# Schematic_v26.net
KiCad netlist of a schematic drawn in EAGLE
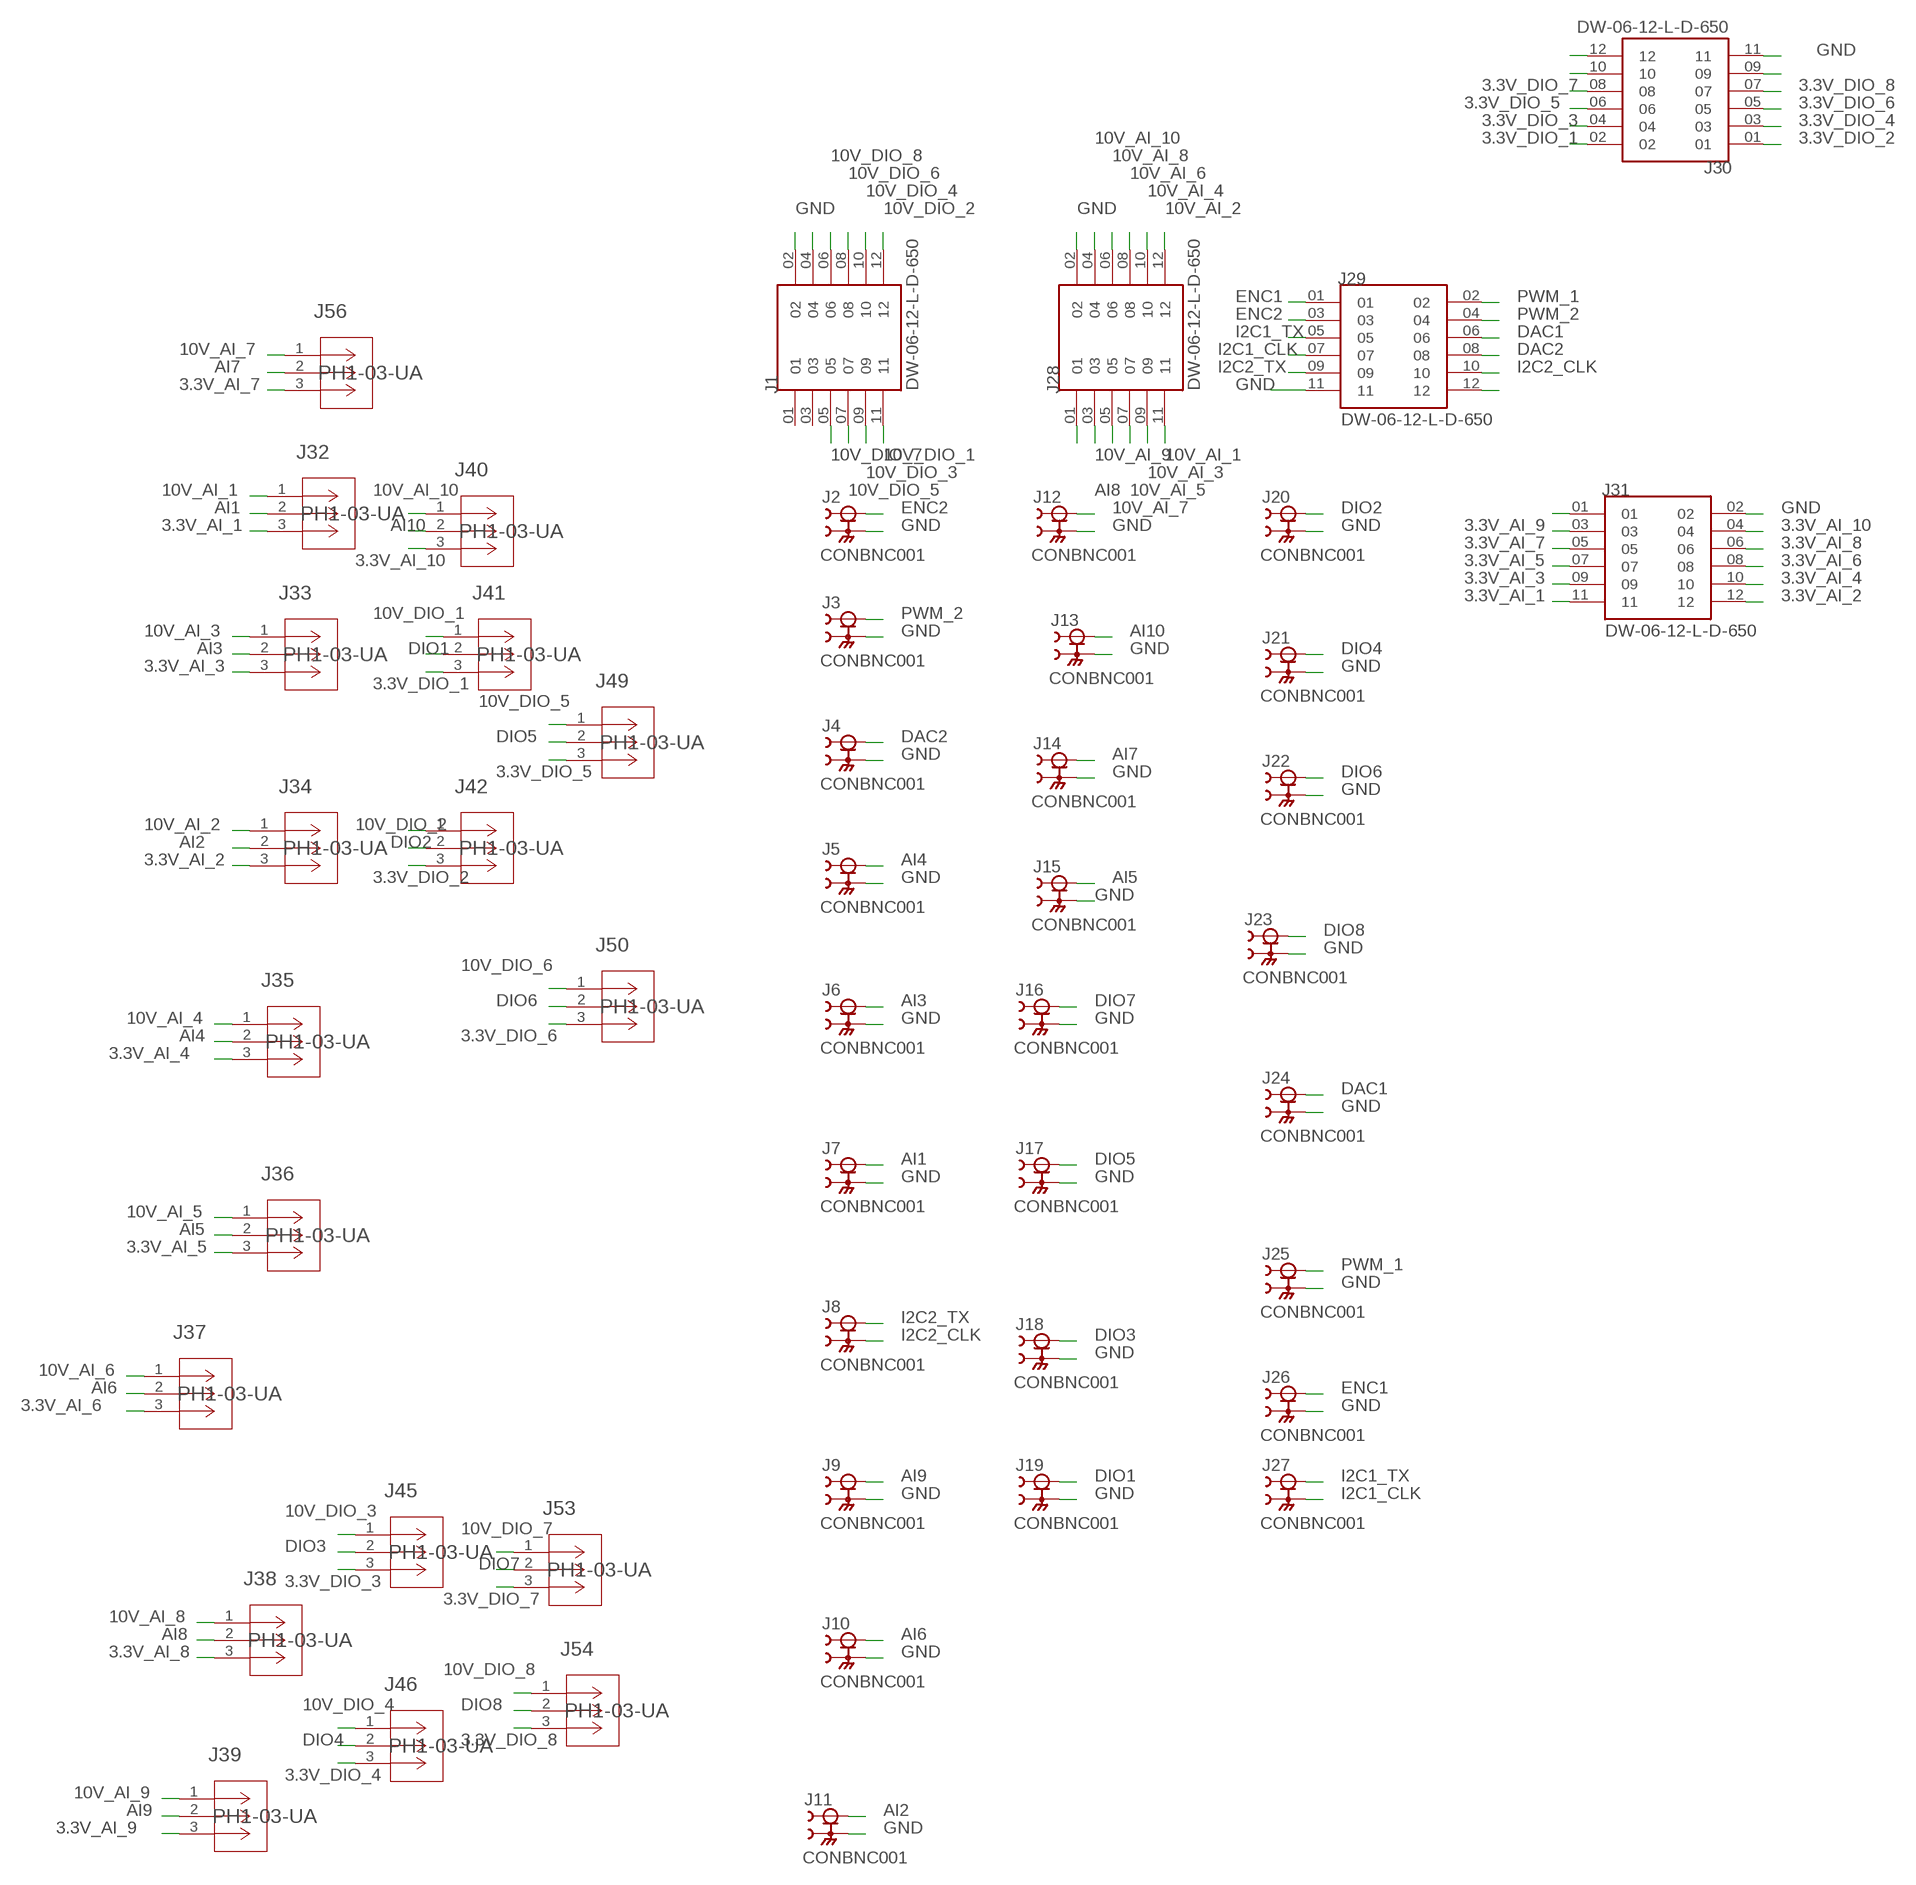
[diagram p0: schematic, sheet 1]

(export (version "E")
  (design (tool "Eeschema 10.0.6"))
  (components
    (comp (ref "J1")
      (value "DW-06-12-L-D-650")
      (footprint "eagle-import:SAMTEC_DW-06-12-L-D-650")
      (fields (field (name "MANUFACTURER") "Samtec"))
      (libsource (lib "eagle-import") (part "DW-06-12-L-D-650"))
    )
    (comp (ref "J2")
      (value "CONBNC001")
      (footprint "eagle-import:LINX_CONBNC001")
      (fields (field (name "MF") "Linx Technologies Inc."))
      (libsource (lib "eagle-import") (part "CONBNC001"))
    )
    (comp (ref "J3")
      (value "CONBNC001")
      (footprint "eagle-import:LINX_CONBNC001")
      (fields (field (name "MF") "Linx Technologies Inc."))
      (libsource (lib "eagle-import") (part "CONBNC001"))
    )
    (comp (ref "J4")
      (value "CONBNC001")
      (footprint "eagle-import:LINX_CONBNC001")
      (fields (field (name "MF") "Linx Technologies Inc."))
      (libsource (lib "eagle-import") (part "CONBNC001"))
    )
    (comp (ref "J5")
      (value "CONBNC001")
      (footprint "eagle-import:LINX_CONBNC001")
      (fields (field (name "MF") "Linx Technologies Inc."))
      (libsource (lib "eagle-import") (part "CONBNC001"))
    )
    (comp (ref "J6")
      (value "CONBNC001")
      (footprint "eagle-import:LINX_CONBNC001")
      (fields (field (name "MF") "Linx Technologies Inc."))
      (libsource (lib "eagle-import") (part "CONBNC001"))
    )
    (comp (ref "J7")
      (value "CONBNC001")
      (footprint "eagle-import:LINX_CONBNC001")
      (fields (field (name "MF") "Linx Technologies Inc."))
      (libsource (lib "eagle-import") (part "CONBNC001"))
    )
    (comp (ref "J8")
      (value "CONBNC001")
      (footprint "eagle-import:LINX_CONBNC001")
      (fields (field (name "MF") "Linx Technologies Inc."))
      (libsource (lib "eagle-import") (part "CONBNC001"))
    )
    (comp (ref "J9")
      (value "CONBNC001")
      (footprint "eagle-import:LINX_CONBNC001")
      (fields (field (name "MF") "Linx Technologies Inc."))
      (libsource (lib "eagle-import") (part "CONBNC001"))
    )
    (comp (ref "J10")
      (value "CONBNC001")
      (footprint "eagle-import:LINX_CONBNC001")
      (fields (field (name "MF") "Linx Technologies Inc."))
      (libsource (lib "eagle-import") (part "CONBNC001"))
    )
    (comp (ref "J11")
      (value "CONBNC001")
      (footprint "eagle-import:LINX_CONBNC001")
      (fields (field (name "MF") "Linx Technologies Inc."))
      (libsource (lib "eagle-import") (part "CONBNC001"))
    )
    (comp (ref "J12")
      (value "CONBNC001")
      (footprint "eagle-import:LINX_CONBNC001")
      (fields (field (name "MF") "Linx Technologies Inc."))
      (libsource (lib "eagle-import") (part "CONBNC001"))
    )
    (comp (ref "J13")
      (value "CONBNC001")
      (footprint "eagle-import:LINX_CONBNC001")
      (fields (field (name "MF") "Linx Technologies Inc."))
      (libsource (lib "eagle-import") (part "CONBNC001"))
    )
    (comp (ref "J14")
      (value "CONBNC001")
      (footprint "eagle-import:LINX_CONBNC001")
      (fields (field (name "MF") "Linx Technologies Inc."))
      (libsource (lib "eagle-import") (part "CONBNC001"))
    )
    (comp (ref "J15")
      (value "CONBNC001")
      (footprint "eagle-import:LINX_CONBNC001")
      (fields (field (name "MF") "Linx Technologies Inc."))
      (libsource (lib "eagle-import") (part "CONBNC001"))
    )
    (comp (ref "J16")
      (value "CONBNC001")
      (footprint "eagle-import:LINX_CONBNC001")
      (fields (field (name "MF") "Linx Technologies Inc."))
      (libsource (lib "eagle-import") (part "CONBNC001"))
    )
    (comp (ref "J17")
      (value "CONBNC001")
      (footprint "eagle-import:LINX_CONBNC001")
      (fields (field (name "MF") "Linx Technologies Inc."))
      (libsource (lib "eagle-import") (part "CONBNC001"))
    )
    (comp (ref "J18")
      (value "CONBNC001")
      (footprint "eagle-import:LINX_CONBNC001")
      (fields (field (name "MF") "Linx Technologies Inc."))
      (libsource (lib "eagle-import") (part "CONBNC001"))
    )
    (comp (ref "J19")
      (value "CONBNC001")
      (footprint "eagle-import:LINX_CONBNC001")
      (fields (field (name "MF") "Linx Technologies Inc."))
      (libsource (lib "eagle-import") (part "CONBNC001"))
    )
    (comp (ref "J20")
      (value "CONBNC001")
      (footprint "eagle-import:LINX_CONBNC001")
      (fields (field (name "MF") "Linx Technologies Inc."))
      (libsource (lib "eagle-import") (part "CONBNC001"))
    )
    (comp (ref "J21")
      (value "CONBNC001")
      (footprint "eagle-import:LINX_CONBNC001")
      (fields (field (name "MF") "Linx Technologies Inc."))
      (libsource (lib "eagle-import") (part "CONBNC001"))
    )
    (comp (ref "J22")
      (value "CONBNC001")
      (footprint "eagle-import:LINX_CONBNC001")
      (fields (field (name "MF") "Linx Technologies Inc."))
      (libsource (lib "eagle-import") (part "CONBNC001"))
    )
    (comp (ref "J23")
      (value "CONBNC001")
      (footprint "eagle-import:LINX_CONBNC001")
      (fields (field (name "MF") "Linx Technologies Inc."))
      (libsource (lib "eagle-import") (part "CONBNC001"))
    )
    (comp (ref "J24")
      (value "CONBNC001")
      (footprint "eagle-import:LINX_CONBNC001")
      (fields (field (name "MF") "Linx Technologies Inc."))
      (libsource (lib "eagle-import") (part "CONBNC001"))
    )
    (comp (ref "J25")
      (value "CONBNC001")
      (footprint "eagle-import:LINX_CONBNC001")
      (fields (field (name "MF") "Linx Technologies Inc."))
      (libsource (lib "eagle-import") (part "CONBNC001"))
    )
    (comp (ref "J26")
      (value "CONBNC001")
      (footprint "eagle-import:LINX_CONBNC001")
      (fields (field (name "MF") "Linx Technologies Inc."))
      (libsource (lib "eagle-import") (part "CONBNC001"))
    )
    (comp (ref "J27")
      (value "CONBNC001")
      (footprint "eagle-import:LINX_CONBNC001")
      (fields (field (name "MF") "Linx Technologies Inc."))
      (libsource (lib "eagle-import") (part "CONBNC001"))
    )
    (comp (ref "J28")
      (value "DW-06-12-L-D-650")
      (footprint "eagle-import:SAMTEC_DW-06-12-L-D-650")
      (fields (field (name "MANUFACTURER") "Samtec"))
      (libsource (lib "eagle-import") (part "DW-06-12-L-D-650"))
    )
    (comp (ref "J29")
      (value "DW-06-12-L-D-650")
      (footprint "eagle-import:SAMTEC_DW-06-12-L-D-650")
      (fields (field (name "MANUFACTURER") "Samtec"))
      (libsource (lib "eagle-import") (part "DW-06-12-L-D-650"))
    )
    (comp (ref "J30")
      (value "DW-06-12-L-D-650")
      (footprint "eagle-import:SAMTEC_DW-06-12-L-D-650")
      (fields (field (name "MANUFACTURER") "Samtec"))
      (libsource (lib "eagle-import") (part "DW-06-12-L-D-650"))
    )
    (comp (ref "J31")
      (value "DW-06-12-L-D-650")
      (footprint "eagle-import:SAMTEC_DW-06-12-L-D-650")
      (fields (field (name "MANUFACTURER") "Samtec"))
      (libsource (lib "eagle-import") (part "DW-06-12-L-D-650"))
    )
    (comp (ref "J32")
      (value "PH1-03-UA")
      (footprint "eagle-import:CONN_PH1-03-UA_ADM")
      (fields (field (name "COPYRIGHT") "Copyright (C) 2025 Ultra Librarian. All rights reserved."))
      (libsource (lib "eagle-import") (part "PH1-03-UA"))
    )
    (comp (ref "J33")
      (value "PH1-03-UA")
      (footprint "eagle-import:CONN_PH1-03-UA_ADM")
      (fields (field (name "COPYRIGHT") "Copyright (C) 2025 Ultra Librarian. All rights reserved."))
      (libsource (lib "eagle-import") (part "PH1-03-UA"))
    )
    (comp (ref "J34")
      (value "PH1-03-UA")
      (footprint "eagle-import:CONN_PH1-03-UA_ADM")
      (fields (field (name "COPYRIGHT") "Copyright (C) 2025 Ultra Librarian. All rights reserved."))
      (libsource (lib "eagle-import") (part "PH1-03-UA"))
    )
    (comp (ref "J35")
      (value "PH1-03-UA")
      (footprint "eagle-import:CONN_PH1-03-UA_ADM")
      (fields (field (name "COPYRIGHT") "Copyright (C) 2025 Ultra Librarian. All rights reserved."))
      (libsource (lib "eagle-import") (part "PH1-03-UA"))
    )
    (comp (ref "J36")
      (value "PH1-03-UA")
      (footprint "eagle-import:CONN_PH1-03-UA_ADM")
      (fields (field (name "COPYRIGHT") "Copyright (C) 2025 Ultra Librarian. All rights reserved."))
      (libsource (lib "eagle-import") (part "PH1-03-UA"))
    )
    (comp (ref "J37")
      (value "PH1-03-UA")
      (footprint "eagle-import:CONN_PH1-03-UA_ADM")
      (fields (field (name "COPYRIGHT") "Copyright (C) 2025 Ultra Librarian. All rights reserved."))
      (libsource (lib "eagle-import") (part "PH1-03-UA"))
    )
    (comp (ref "J38")
      (value "PH1-03-UA")
      (footprint "eagle-import:CONN_PH1-03-UA_ADM")
      (fields (field (name "COPYRIGHT") "Copyright (C) 2025 Ultra Librarian. All rights reserved."))
      (libsource (lib "eagle-import") (part "PH1-03-UA"))
    )
    (comp (ref "J39")
      (value "PH1-03-UA")
      (footprint "eagle-import:CONN_PH1-03-UA_ADM")
      (fields (field (name "COPYRIGHT") "Copyright (C) 2025 Ultra Librarian. All rights reserved."))
      (libsource (lib "eagle-import") (part "PH1-03-UA"))
    )
    (comp (ref "J40")
      (value "PH1-03-UA")
      (footprint "eagle-import:CONN_PH1-03-UA_ADM")
      (fields (field (name "COPYRIGHT") "Copyright (C) 2025 Ultra Librarian. All rights reserved."))
      (libsource (lib "eagle-import") (part "PH1-03-UA"))
    )
    (comp (ref "J41")
      (value "PH1-03-UA")
      (footprint "eagle-import:CONN_PH1-03-UA_ADM")
      (fields (field (name "COPYRIGHT") "Copyright (C) 2025 Ultra Librarian. All rights reserved."))
      (libsource (lib "eagle-import") (part "PH1-03-UA"))
    )
    (comp (ref "J42")
      (value "PH1-03-UA")
      (footprint "eagle-import:CONN_PH1-03-UA_ADM")
      (fields (field (name "COPYRIGHT") "Copyright (C) 2025 Ultra Librarian. All rights reserved."))
      (libsource (lib "eagle-import") (part "PH1-03-UA"))
    )
    (comp (ref "J45")
      (value "PH1-03-UA")
      (footprint "eagle-import:CONN_PH1-03-UA_ADM")
      (fields (field (name "COPYRIGHT") "Copyright (C) 2025 Ultra Librarian. All rights reserved."))
      (libsource (lib "eagle-import") (part "PH1-03-UA"))
    )
    (comp (ref "J46")
      (value "PH1-03-UA")
      (footprint "eagle-import:CONN_PH1-03-UA_ADM")
      (fields (field (name "COPYRIGHT") "Copyright (C) 2025 Ultra Librarian. All rights reserved."))
      (libsource (lib "eagle-import") (part "PH1-03-UA"))
    )
    (comp (ref "J49")
      (value "PH1-03-UA")
      (footprint "eagle-import:CONN_PH1-03-UA_ADM")
      (fields (field (name "COPYRIGHT") "Copyright (C) 2025 Ultra Librarian. All rights reserved."))
      (libsource (lib "eagle-import") (part "PH1-03-UA"))
    )
    (comp (ref "J50")
      (value "PH1-03-UA")
      (footprint "eagle-import:CONN_PH1-03-UA_ADM")
      (fields (field (name "COPYRIGHT") "Copyright (C) 2025 Ultra Librarian. All rights reserved."))
      (libsource (lib "eagle-import") (part "PH1-03-UA"))
    )
    (comp (ref "J53")
      (value "PH1-03-UA")
      (footprint "eagle-import:CONN_PH1-03-UA_ADM")
      (fields (field (name "COPYRIGHT") "Copyright (C) 2025 Ultra Librarian. All rights reserved."))
      (libsource (lib "eagle-import") (part "PH1-03-UA"))
    )
    (comp (ref "J54")
      (value "PH1-03-UA")
      (footprint "eagle-import:CONN_PH1-03-UA_ADM")
      (fields (field (name "COPYRIGHT") "Copyright (C) 2025 Ultra Librarian. All rights reserved."))
      (libsource (lib "eagle-import") (part "PH1-03-UA"))
    )
    (comp (ref "J56")
      (value "PH1-03-UA")
      (footprint "eagle-import:CONN_PH1-03-UA_ADM")
      (fields (field (name "COPYRIGHT") "Copyright (C) 2025 Ultra Librarian. All rights reserved."))
      (libsource (lib "eagle-import") (part "PH1-03-UA"))
    )
  )
  (nets
    (net (code "1") (name "/3.3V_AI_1") (class "Default")
      (node (ref "J31") (pin "11") (pinfunction "11_11") (pintype "passive"))
      (node (ref "J32") (pin "3") (pinfunction "3_3") (pintype "passive"))
    )
    (net (code "2") (name "/3.3V_AI_2") (class "Default")
      (node (ref "J31") (pin "12") (pinfunction "12_12") (pintype "passive"))
      (node (ref "J34") (pin "3") (pinfunction "3_3") (pintype "passive"))
    )
    (net (code "3") (name "/3.3V_AI_3") (class "Default")
      (node (ref "J31") (pin "09") (pinfunction "09_09") (pintype "passive"))
      (node (ref "J33") (pin "3") (pinfunction "3_3") (pintype "passive"))
    )
    (net (code "4") (name "/3.3V_AI_4") (class "Default")
      (node (ref "J31") (pin "10") (pinfunction "10_10") (pintype "passive"))
      (node (ref "J35") (pin "3") (pinfunction "3_3") (pintype "passive"))
    )
    (net (code "5") (name "/3.3V_AI_5") (class "Default")
      (node (ref "J31") (pin "07") (pinfunction "07_07") (pintype "passive"))
      (node (ref "J36") (pin "3") (pinfunction "3_3") (pintype "passive"))
    )
    (net (code "6") (name "/3.3V_AI_6") (class "Default")
      (node (ref "J31") (pin "08") (pinfunction "08_08") (pintype "passive"))
      (node (ref "J37") (pin "3") (pinfunction "3_3") (pintype "passive"))
    )
    (net (code "7") (name "/3.3V_AI_7") (class "Default")
      (node (ref "J31") (pin "05") (pinfunction "05_05") (pintype "passive"))
      (node (ref "J56") (pin "3") (pinfunction "3_3") (pintype "passive"))
    )
    (net (code "8") (name "/3.3V_AI_8") (class "Default")
      (node (ref "J31") (pin "06") (pinfunction "06_06") (pintype "passive"))
      (node (ref "J38") (pin "3") (pinfunction "3_3") (pintype "passive"))
    )
    (net (code "9") (name "/3.3V_AI_9") (class "Default")
      (node (ref "J31") (pin "03") (pinfunction "03_03") (pintype "passive"))
      (node (ref "J39") (pin "3") (pinfunction "3_3") (pintype "passive"))
    )
    (net (code "10") (name "/3.3V_AI_10") (class "Default")
      (node (ref "J31") (pin "04") (pinfunction "04_04") (pintype "passive"))
      (node (ref "J40") (pin "3") (pinfunction "3_3") (pintype "passive"))
    )
    (net (code "11") (name "/3.3V_DIO_1") (class "Default")
      (node (ref "J30") (pin "02") (pinfunction "02_02") (pintype "passive"))
      (node (ref "J41") (pin "3") (pinfunction "3_3") (pintype "passive"))
    )
    (net (code "12") (name "/3.3V_DIO_2") (class "Default")
      (node (ref "J30") (pin "01") (pinfunction "01_01") (pintype "passive"))
      (node (ref "J42") (pin "3") (pinfunction "3_3") (pintype "passive"))
    )
    (net (code "13") (name "/3.3V_DIO_3") (class "Default")
      (node (ref "J30") (pin "04") (pinfunction "04_04") (pintype "passive"))
      (node (ref "J45") (pin "3") (pinfunction "3_3") (pintype "passive"))
    )
    (net (code "14") (name "/3.3V_DIO_4") (class "Default")
      (node (ref "J30") (pin "03") (pinfunction "03_03") (pintype "passive"))
      (node (ref "J46") (pin "3") (pinfunction "3_3") (pintype "passive"))
    )
    (net (code "15") (name "/3.3V_DIO_5") (class "Default")
      (node (ref "J30") (pin "06") (pinfunction "06_06") (pintype "passive"))
      (node (ref "J49") (pin "3") (pinfunction "3_3") (pintype "passive"))
    )
    (net (code "16") (name "/3.3V_DIO_6") (class "Default")
      (node (ref "J30") (pin "05") (pinfunction "05_05") (pintype "passive"))
      (node (ref "J50") (pin "3") (pinfunction "3_3") (pintype "passive"))
    )
    (net (code "17") (name "/3.3V_DIO_7") (class "Default")
      (node (ref "J30") (pin "08") (pinfunction "08_08") (pintype "passive"))
      (node (ref "J53") (pin "3") (pinfunction "3_3") (pintype "passive"))
    )
    (net (code "18") (name "/3.3V_DIO_8") (class "Default")
      (node (ref "J30") (pin "07") (pinfunction "07_07") (pintype "passive"))
      (node (ref "J54") (pin "3") (pinfunction "3_3") (pintype "passive"))
    )
    (net (code "19") (name "/10V_AI_1") (class "Default")
      (node (ref "J28") (pin "11") (pinfunction "11_11") (pintype "passive"))
      (node (ref "J32") (pin "1") (pinfunction "1_1") (pintype "passive"))
    )
    (net (code "20") (name "/10V_AI_2") (class "Default")
      (node (ref "J28") (pin "12") (pinfunction "12_12") (pintype "passive"))
      (node (ref "J34") (pin "1") (pinfunction "1_1") (pintype "passive"))
    )
    (net (code "21") (name "/10V_AI_3") (class "Default")
      (node (ref "J28") (pin "09") (pinfunction "09_09") (pintype "passive"))
      (node (ref "J33") (pin "1") (pinfunction "1_1") (pintype "passive"))
    )
    (net (code "22") (name "/10V_AI_4") (class "Default")
      (node (ref "J28") (pin "10") (pinfunction "10_10") (pintype "passive"))
      (node (ref "J35") (pin "1") (pinfunction "1_1") (pintype "passive"))
    )
    (net (code "23") (name "/10V_AI_5") (class "Default")
      (node (ref "J28") (pin "07") (pinfunction "07_07") (pintype "passive"))
      (node (ref "J36") (pin "1") (pinfunction "1_1") (pintype "passive"))
    )
    (net (code "24") (name "/10V_AI_6") (class "Default")
      (node (ref "J28") (pin "08") (pinfunction "08_08") (pintype "passive"))
      (node (ref "J37") (pin "1") (pinfunction "1_1") (pintype "passive"))
    )
    (net (code "25") (name "/10V_AI_7") (class "Default")
      (node (ref "J28") (pin "05") (pinfunction "05_05") (pintype "passive"))
      (node (ref "J56") (pin "1") (pinfunction "1_1") (pintype "passive"))
    )
    (net (code "26") (name "/10V_AI_8") (class "Default")
      (node (ref "J28") (pin "06") (pinfunction "06_06") (pintype "passive"))
      (node (ref "J38") (pin "1") (pinfunction "1_1") (pintype "passive"))
    )
    (net (code "27") (name "/10V_AI_9") (class "Default")
      (node (ref "J28") (pin "03") (pinfunction "03_03") (pintype "passive"))
      (node (ref "J39") (pin "1") (pinfunction "1_1") (pintype "passive"))
    )
    (net (code "28") (name "/10V_AI_10") (class "Default")
      (node (ref "J28") (pin "04") (pinfunction "04_04") (pintype "passive"))
      (node (ref "J40") (pin "1") (pinfunction "1_1") (pintype "passive"))
    )
    (net (code "29") (name "/10V_DIO_1") (class "Default")
      (node (ref "J1") (pin "11") (pinfunction "11_11") (pintype "passive"))
      (node (ref "J41") (pin "1") (pinfunction "1_1") (pintype "passive"))
    )
    (net (code "30") (name "/10V_DIO_2") (class "Default")
      (node (ref "J1") (pin "12") (pinfunction "12_12") (pintype "passive"))
      (node (ref "J42") (pin "1") (pinfunction "1_1") (pintype "passive"))
    )
    (net (code "31") (name "/10V_DIO_3") (class "Default")
      (node (ref "J1") (pin "09") (pinfunction "09_09") (pintype "passive"))
      (node (ref "J45") (pin "1") (pinfunction "1_1") (pintype "passive"))
    )
    (net (code "32") (name "/10V_DIO_4") (class "Default")
      (node (ref "J1") (pin "10") (pinfunction "10_10") (pintype "passive"))
      (node (ref "J46") (pin "1") (pinfunction "1_1") (pintype "passive"))
    )
    (net (code "33") (name "/10V_DIO_5") (class "Default")
      (node (ref "J1") (pin "07") (pinfunction "07_07") (pintype "passive"))
      (node (ref "J49") (pin "1") (pinfunction "1_1") (pintype "passive"))
    )
    (net (code "34") (name "/10V_DIO_6") (class "Default")
      (node (ref "J1") (pin "08") (pinfunction "08_08") (pintype "passive"))
      (node (ref "J50") (pin "1") (pinfunction "1_1") (pintype "passive"))
    )
    (net (code "35") (name "/10V_DIO_7") (class "Default")
      (node (ref "J1") (pin "05") (pinfunction "05_05") (pintype "passive"))
      (node (ref "J53") (pin "1") (pinfunction "1_1") (pintype "passive"))
    )
    (net (code "36") (name "/10V_DIO_8") (class "Default")
      (node (ref "J1") (pin "06") (pinfunction "06_06") (pintype "passive"))
      (node (ref "J54") (pin "1") (pinfunction "1_1") (pintype "passive"))
    )
    (net (code "37") (name "/AI1") (class "Default")
      (node (ref "J32") (pin "2") (pinfunction "2_2") (pintype "passive"))
      (node (ref "J7") (pin "1") (pinfunction "1_1") (pintype "passive"))
    )
    (net (code "38") (name "/AI2") (class "Default")
      (node (ref "J11") (pin "1") (pinfunction "1_1") (pintype "passive"))
      (node (ref "J34") (pin "2") (pinfunction "2_2") (pintype "passive"))
    )
    (net (code "39") (name "/AI3") (class "Default")
      (node (ref "J33") (pin "2") (pinfunction "2_2") (pintype "passive"))
      (node (ref "J6") (pin "1") (pinfunction "1_1") (pintype "passive"))
    )
    (net (code "40") (name "/AI4") (class "Default")
      (node (ref "J35") (pin "2") (pinfunction "2_2") (pintype "passive"))
      (node (ref "J5") (pin "1") (pinfunction "1_1") (pintype "passive"))
    )
    (net (code "41") (name "/AI5") (class "Default")
      (node (ref "J15") (pin "1") (pinfunction "1_1") (pintype "passive"))
      (node (ref "J36") (pin "2") (pinfunction "2_2") (pintype "passive"))
    )
    (net (code "42") (name "/AI6") (class "Default")
      (node (ref "J10") (pin "1") (pinfunction "1_1") (pintype "passive"))
      (node (ref "J37") (pin "2") (pinfunction "2_2") (pintype "passive"))
    )
    (net (code "43") (name "/AI7") (class "Default")
      (node (ref "J14") (pin "1") (pinfunction "1_1") (pintype "passive"))
      (node (ref "J56") (pin "2") (pinfunction "2_2") (pintype "passive"))
    )
    (net (code "44") (name "/AI8") (class "Default")
      (node (ref "J12") (pin "1") (pinfunction "1_1") (pintype "passive"))
      (node (ref "J38") (pin "2") (pinfunction "2_2") (pintype "passive"))
    )
    (net (code "45") (name "/AI9") (class "Default")
      (node (ref "J39") (pin "2") (pinfunction "2_2") (pintype "passive"))
      (node (ref "J9") (pin "1") (pinfunction "1_1") (pintype "passive"))
    )
    (net (code "46") (name "/AI10") (class "Default")
      (node (ref "J13") (pin "1") (pinfunction "1_1") (pintype "passive"))
      (node (ref "J40") (pin "2") (pinfunction "2_2") (pintype "passive"))
    )
    (net (code "47") (name "/DAC1") (class "Default")
      (node (ref "J24") (pin "1") (pinfunction "1_1") (pintype "passive"))
      (node (ref "J29") (pin "06") (pinfunction "06_06") (pintype "passive"))
    )
    (net (code "48") (name "/DAC2") (class "Default")
      (node (ref "J29") (pin "08") (pinfunction "08_08") (pintype "passive"))
      (node (ref "J4") (pin "1") (pinfunction "1_1") (pintype "passive"))
    )
    (net (code "49") (name "/DIO1") (class "Default")
      (node (ref "J19") (pin "1") (pinfunction "1_1") (pintype "passive"))
      (node (ref "J41") (pin "2") (pinfunction "2_2") (pintype "passive"))
    )
    (net (code "50") (name "/DIO2") (class "Default")
      (node (ref "J20") (pin "1") (pinfunction "1_1") (pintype "passive"))
      (node (ref "J42") (pin "2") (pinfunction "2_2") (pintype "passive"))
    )
    (net (code "51") (name "/DIO3") (class "Default")
      (node (ref "J18") (pin "1") (pinfunction "1_1") (pintype "passive"))
      (node (ref "J45") (pin "2") (pinfunction "2_2") (pintype "passive"))
    )
    (net (code "52") (name "/DIO4") (class "Default")
      (node (ref "J21") (pin "1") (pinfunction "1_1") (pintype "passive"))
      (node (ref "J46") (pin "2") (pinfunction "2_2") (pintype "passive"))
    )
    (net (code "53") (name "/DIO5") (class "Default")
      (node (ref "J17") (pin "1") (pinfunction "1_1") (pintype "passive"))
      (node (ref "J49") (pin "2") (pinfunction "2_2") (pintype "passive"))
    )
    (net (code "54") (name "/DIO6") (class "Default")
      (node (ref "J22") (pin "1") (pinfunction "1_1") (pintype "passive"))
      (node (ref "J50") (pin "2") (pinfunction "2_2") (pintype "passive"))
    )
    (net (code "55") (name "/DIO7") (class "Default")
      (node (ref "J16") (pin "1") (pinfunction "1_1") (pintype "passive"))
      (node (ref "J53") (pin "2") (pinfunction "2_2") (pintype "passive"))
    )
    (net (code "56") (name "/DIO8") (class "Default")
      (node (ref "J23") (pin "1") (pinfunction "1_1") (pintype "passive"))
      (node (ref "J54") (pin "2") (pinfunction "2_2") (pintype "passive"))
    )
    (net (code "57") (name "/ENC1") (class "Default")
      (node (ref "J26") (pin "1") (pinfunction "1_1") (pintype "passive"))
      (node (ref "J29") (pin "01") (pinfunction "01_01") (pintype "passive"))
    )
    (net (code "58") (name "/ENC2") (class "Default")
      (node (ref "J2") (pin "1") (pinfunction "1_1") (pintype "passive"))
      (node (ref "J29") (pin "03") (pinfunction "03_03") (pintype "passive"))
    )
    (net (code "59") (name "/GND") (class "Default")
      (node (ref "J1") (pin "02") (pinfunction "02_02") (pintype "passive"))
      (node (ref "J10") (pin "S1") (pinfunction "2_S1") (pintype "passive"))
      (node (ref "J10") (pin "S2") (pinfunction "2_S2") (pintype "passive"))
      (node (ref "J10") (pin "S3") (pinfunction "2_S3") (pintype "passive"))
      (node (ref "J10") (pin "S4") (pinfunction "2_S4") (pintype "passive"))
      (node (ref "J11") (pin "S1") (pinfunction "2_S1") (pintype "passive"))
      (node (ref "J11") (pin "S2") (pinfunction "2_S2") (pintype "passive"))
      (node (ref "J11") (pin "S3") (pinfunction "2_S3") (pintype "passive"))
      (node (ref "J11") (pin "S4") (pinfunction "2_S4") (pintype "passive"))
      (node (ref "J12") (pin "S1") (pinfunction "2_S1") (pintype "passive"))
      (node (ref "J12") (pin "S2") (pinfunction "2_S2") (pintype "passive"))
      (node (ref "J12") (pin "S3") (pinfunction "2_S3") (pintype "passive"))
      (node (ref "J12") (pin "S4") (pinfunction "2_S4") (pintype "passive"))
      (node (ref "J13") (pin "S1") (pinfunction "2_S1") (pintype "passive"))
      (node (ref "J13") (pin "S2") (pinfunction "2_S2") (pintype "passive"))
      (node (ref "J13") (pin "S3") (pinfunction "2_S3") (pintype "passive"))
      (node (ref "J13") (pin "S4") (pinfunction "2_S4") (pintype "passive"))
      (node (ref "J14") (pin "S1") (pinfunction "2_S1") (pintype "passive"))
      (node (ref "J14") (pin "S2") (pinfunction "2_S2") (pintype "passive"))
      (node (ref "J14") (pin "S3") (pinfunction "2_S3") (pintype "passive"))
      (node (ref "J14") (pin "S4") (pinfunction "2_S4") (pintype "passive"))
      (node (ref "J15") (pin "S1") (pinfunction "2_S1") (pintype "passive"))
      (node (ref "J15") (pin "S2") (pinfunction "2_S2") (pintype "passive"))
      (node (ref "J15") (pin "S3") (pinfunction "2_S3") (pintype "passive"))
      (node (ref "J15") (pin "S4") (pinfunction "2_S4") (pintype "passive"))
      (node (ref "J16") (pin "S1") (pinfunction "2_S1") (pintype "passive"))
      (node (ref "J16") (pin "S2") (pinfunction "2_S2") (pintype "passive"))
      (node (ref "J16") (pin "S3") (pinfunction "2_S3") (pintype "passive"))
      (node (ref "J16") (pin "S4") (pinfunction "2_S4") (pintype "passive"))
      (node (ref "J17") (pin "S1") (pinfunction "2_S1") (pintype "passive"))
      (node (ref "J17") (pin "S2") (pinfunction "2_S2") (pintype "passive"))
      (node (ref "J17") (pin "S3") (pinfunction "2_S3") (pintype "passive"))
      (node (ref "J17") (pin "S4") (pinfunction "2_S4") (pintype "passive"))
      (node (ref "J18") (pin "S1") (pinfunction "2_S1") (pintype "passive"))
      (node (ref "J18") (pin "S2") (pinfunction "2_S2") (pintype "passive"))
      (node (ref "J18") (pin "S3") (pinfunction "2_S3") (pintype "passive"))
      (node (ref "J18") (pin "S4") (pinfunction "2_S4") (pintype "passive"))
      (node (ref "J19") (pin "S1") (pinfunction "2_S1") (pintype "passive"))
      (node (ref "J19") (pin "S2") (pinfunction "2_S2") (pintype "passive"))
      (node (ref "J19") (pin "S3") (pinfunction "2_S3") (pintype "passive"))
      (node (ref "J19") (pin "S4") (pinfunction "2_S4") (pintype "passive"))
      (node (ref "J2") (pin "S1") (pinfunction "2_S1") (pintype "passive"))
      (node (ref "J2") (pin "S2") (pinfunction "2_S2") (pintype "passive"))
      (node (ref "J2") (pin "S3") (pinfunction "2_S3") (pintype "passive"))
      (node (ref "J2") (pin "S4") (pinfunction "2_S4") (pintype "passive"))
      (node (ref "J20") (pin "S1") (pinfunction "2_S1") (pintype "passive"))
      (node (ref "J20") (pin "S2") (pinfunction "2_S2") (pintype "passive"))
      (node (ref "J20") (pin "S3") (pinfunction "2_S3") (pintype "passive"))
      (node (ref "J20") (pin "S4") (pinfunction "2_S4") (pintype "passive"))
      (node (ref "J21") (pin "S1") (pinfunction "2_S1") (pintype "passive"))
      (node (ref "J21") (pin "S2") (pinfunction "2_S2") (pintype "passive"))
      (node (ref "J21") (pin "S3") (pinfunction "2_S3") (pintype "passive"))
      (node (ref "J21") (pin "S4") (pinfunction "2_S4") (pintype "passive"))
      (node (ref "J22") (pin "S1") (pinfunction "2_S1") (pintype "passive"))
      (node (ref "J22") (pin "S2") (pinfunction "2_S2") (pintype "passive"))
      (node (ref "J22") (pin "S3") (pinfunction "2_S3") (pintype "passive"))
      (node (ref "J22") (pin "S4") (pinfunction "2_S4") (pintype "passive"))
      (node (ref "J23") (pin "S1") (pinfunction "2_S1") (pintype "passive"))
      (node (ref "J23") (pin "S2") (pinfunction "2_S2") (pintype "passive"))
      (node (ref "J23") (pin "S3") (pinfunction "2_S3") (pintype "passive"))
      (node (ref "J23") (pin "S4") (pinfunction "2_S4") (pintype "passive"))
      (node (ref "J24") (pin "S1") (pinfunction "2_S1") (pintype "passive"))
      (node (ref "J24") (pin "S2") (pinfunction "2_S2") (pintype "passive"))
      (node (ref "J24") (pin "S3") (pinfunction "2_S3") (pintype "passive"))
      (node (ref "J24") (pin "S4") (pinfunction "2_S4") (pintype "passive"))
      (node (ref "J25") (pin "S1") (pinfunction "2_S1") (pintype "passive"))
      (node (ref "J25") (pin "S2") (pinfunction "2_S2") (pintype "passive"))
      (node (ref "J25") (pin "S3") (pinfunction "2_S3") (pintype "passive"))
      (node (ref "J25") (pin "S4") (pinfunction "2_S4") (pintype "passive"))
      (node (ref "J26") (pin "S1") (pinfunction "2_S1") (pintype "passive"))
      (node (ref "J26") (pin "S2") (pinfunction "2_S2") (pintype "passive"))
      (node (ref "J26") (pin "S3") (pinfunction "2_S3") (pintype "passive"))
      (node (ref "J26") (pin "S4") (pinfunction "2_S4") (pintype "passive"))
      (node (ref "J28") (pin "02") (pinfunction "02_02") (pintype "passive"))
      (node (ref "J29") (pin "11") (pinfunction "11_11") (pintype "passive"))
      (node (ref "J3") (pin "S1") (pinfunction "2_S1") (pintype "passive"))
      (node (ref "J3") (pin "S2") (pinfunction "2_S2") (pintype "passive"))
      (node (ref "J3") (pin "S3") (pinfunction "2_S3") (pintype "passive"))
      (node (ref "J3") (pin "S4") (pinfunction "2_S4") (pintype "passive"))
      (node (ref "J30") (pin "11") (pinfunction "11_11") (pintype "passive"))
      (node (ref "J31") (pin "02") (pinfunction "02_02") (pintype "passive"))
      (node (ref "J4") (pin "S1") (pinfunction "2_S1") (pintype "passive"))
      (node (ref "J4") (pin "S2") (pinfunction "2_S2") (pintype "passive"))
      (node (ref "J4") (pin "S3") (pinfunction "2_S3") (pintype "passive"))
      (node (ref "J4") (pin "S4") (pinfunction "2_S4") (pintype "passive"))
      (node (ref "J5") (pin "S1") (pinfunction "2_S1") (pintype "passive"))
      (node (ref "J5") (pin "S2") (pinfunction "2_S2") (pintype "passive"))
      (node (ref "J5") (pin "S3") (pinfunction "2_S3") (pintype "passive"))
      (node (ref "J5") (pin "S4") (pinfunction "2_S4") (pintype "passive"))
      (node (ref "J6") (pin "S1") (pinfunction "2_S1") (pintype "passive"))
      (node (ref "J6") (pin "S2") (pinfunction "2_S2") (pintype "passive"))
      (node (ref "J6") (pin "S3") (pinfunction "2_S3") (pintype "passive"))
      (node (ref "J6") (pin "S4") (pinfunction "2_S4") (pintype "passive"))
      (node (ref "J7") (pin "S1") (pinfunction "2_S1") (pintype "passive"))
      (node (ref "J7") (pin "S2") (pinfunction "2_S2") (pintype "passive"))
      (node (ref "J7") (pin "S3") (pinfunction "2_S3") (pintype "passive"))
      (node (ref "J7") (pin "S4") (pinfunction "2_S4") (pintype "passive"))
      (node (ref "J9") (pin "S1") (pinfunction "2_S1") (pintype "passive"))
      (node (ref "J9") (pin "S2") (pinfunction "2_S2") (pintype "passive"))
      (node (ref "J9") (pin "S3") (pinfunction "2_S3") (pintype "passive"))
      (node (ref "J9") (pin "S4") (pinfunction "2_S4") (pintype "passive"))
    )
    (net (code "60") (name "/I2C1_CLK") (class "Default")
      (node (ref "J27") (pin "S1") (pinfunction "2_S1") (pintype "passive"))
      (node (ref "J27") (pin "S2") (pinfunction "2_S2") (pintype "passive"))
      (node (ref "J27") (pin "S3") (pinfunction "2_S3") (pintype "passive"))
      (node (ref "J27") (pin "S4") (pinfunction "2_S4") (pintype "passive"))
      (node (ref "J29") (pin "07") (pinfunction "07_07") (pintype "passive"))
    )
    (net (code "61") (name "/I2C1_TX") (class "Default")
      (node (ref "J27") (pin "1") (pinfunction "1_1") (pintype "passive"))
      (node (ref "J29") (pin "05") (pinfunction "05_05") (pintype "passive"))
    )
    (net (code "62") (name "/I2C2_CLK") (class "Default")
      (node (ref "J29") (pin "10") (pinfunction "10_10") (pintype "passive"))
      (node (ref "J8") (pin "S1") (pinfunction "2_S1") (pintype "passive"))
      (node (ref "J8") (pin "S2") (pinfunction "2_S2") (pintype "passive"))
      (node (ref "J8") (pin "S3") (pinfunction "2_S3") (pintype "passive"))
      (node (ref "J8") (pin "S4") (pinfunction "2_S4") (pintype "passive"))
    )
    (net (code "63") (name "/I2C2_TX") (class "Default")
      (node (ref "J29") (pin "09") (pinfunction "09_09") (pintype "passive"))
      (node (ref "J8") (pin "1") (pinfunction "1_1") (pintype "passive"))
    )
    (net (code "64") (name "/PWM_1") (class "Default")
      (node (ref "J25") (pin "1") (pinfunction "1_1") (pintype "passive"))
      (node (ref "J29") (pin "02") (pinfunction "02_02") (pintype "passive"))
    )
    (net (code "65") (name "/PWM_2") (class "Default")
      (node (ref "J29") (pin "04") (pinfunction "04_04") (pintype "passive"))
      (node (ref "J3") (pin "1") (pinfunction "1_1") (pintype "passive"))
    )
    (net (code "66") (name "unconnected-(J1-Pad01)") (class "Default")
      (node (ref "J1") (pin "01") (pinfunction "01_01") (pintype "passive"))
    )
    (net (code "67") (name "unconnected-(J1-Pad03)") (class "Default")
      (node (ref "J1") (pin "03") (pinfunction "03_03") (pintype "passive"))
    )
    (net (code "68") (name "unconnected-(J1-Pad04)") (class "Default")
      (node (ref "J1") (pin "04") (pinfunction "04_04") (pintype "passive"))
    )
    (net (code "69") (name "unconnected-(J28-Pad01)") (class "Default")
      (node (ref "J28") (pin "01") (pinfunction "01_01") (pintype "passive"))
    )
    (net (code "70") (name "unconnected-(J29-Pad12)") (class "Default")
      (node (ref "J29") (pin "12") (pinfunction "12_12") (pintype "passive"))
    )
    (net (code "71") (name "unconnected-(J30-Pad09)") (class "Default")
      (node (ref "J30") (pin "09") (pinfunction "09_09") (pintype "passive"))
    )
    (net (code "72") (name "unconnected-(J30-Pad10)") (class "Default")
      (node (ref "J30") (pin "10") (pinfunction "10_10") (pintype "passive"))
    )
    (net (code "73") (name "unconnected-(J30-Pad12)") (class "Default")
      (node (ref "J30") (pin "12") (pinfunction "12_12") (pintype "passive"))
    )
    (net (code "74") (name "unconnected-(J31-Pad01)") (class "Default")
      (node (ref "J31") (pin "01") (pinfunction "01_01") (pintype "passive"))
    )
  )
)
